# logger_connector.net
KiCad netlist of a schematic drawn in Altium Designer
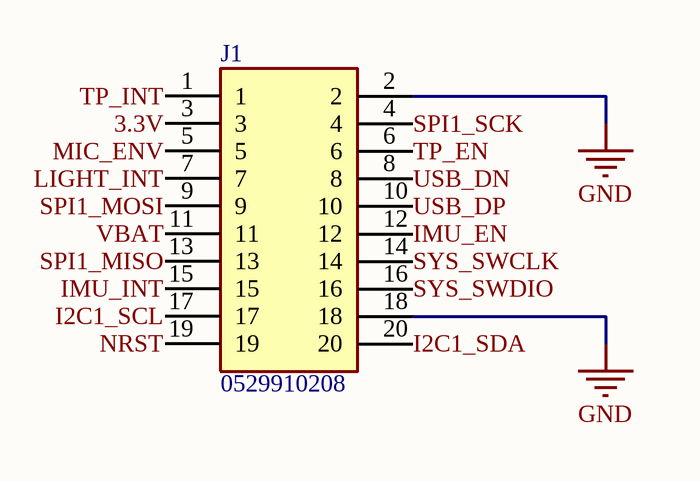
[diagram p0: logger_connector.SchDoc]

(export (version "E")
  (design (tool "Eeschema 10.0.6"))
  (components
    (comp (ref "J1")
      (value "0529910208")
      (footprint "SamacSys:0529910208")
      (description "Connector")
      (libsource (lib "*") (part "0529910208"))
    )
  )
  (nets
    (net (code "1") (name "/3.3V") (class "Default")
      (node (ref "J1") (pin "3") (pinfunction "3_3") (pintype "passive"))
    )
    (net (code "2") (name "/I2C1_SCL") (class "Default")
      (node (ref "J1") (pin "17") (pinfunction "17_17") (pintype "passive"))
    )
    (net (code "3") (name "/I2C1_SDA") (class "Default")
      (node (ref "J1") (pin "20") (pinfunction "20_20") (pintype "passive"))
    )
    (net (code "4") (name "/IMU_EN") (class "Default")
      (node (ref "J1") (pin "12") (pinfunction "12_12") (pintype "passive"))
    )
    (net (code "5") (name "/IMU_INT") (class "Default")
      (node (ref "J1") (pin "15") (pinfunction "15_15") (pintype "passive"))
    )
    (net (code "6") (name "/LIGHT_INT") (class "Default")
      (node (ref "J1") (pin "7") (pinfunction "7_7") (pintype "passive"))
    )
    (net (code "7") (name "/MIC_ENV") (class "Default")
      (node (ref "J1") (pin "5") (pinfunction "5_5") (pintype "passive"))
    )
    (net (code "8") (name "/NRST") (class "Default")
      (node (ref "J1") (pin "19") (pinfunction "19_19") (pintype "passive"))
    )
    (net (code "9") (name "/SPI1_MISO") (class "Default")
      (node (ref "J1") (pin "13") (pinfunction "13_13") (pintype "passive"))
    )
    (net (code "10") (name "/SPI1_MOSI") (class "Default")
      (node (ref "J1") (pin "9") (pinfunction "9_9") (pintype "passive"))
    )
    (net (code "11") (name "/SPI1_SCK") (class "Default")
      (node (ref "J1") (pin "4") (pinfunction "4_4") (pintype "passive"))
    )
    (net (code "12") (name "/SYS_SWCLK") (class "Default")
      (node (ref "J1") (pin "14") (pinfunction "14_14") (pintype "passive"))
    )
    (net (code "13") (name "/SYS_SWDIO") (class "Default")
      (node (ref "J1") (pin "16") (pinfunction "16_16") (pintype "passive"))
    )
    (net (code "14") (name "/TP_EN") (class "Default")
      (node (ref "J1") (pin "6") (pinfunction "6_6") (pintype "passive"))
    )
    (net (code "15") (name "/TP_INT") (class "Default")
      (node (ref "J1") (pin "1") (pinfunction "1_1") (pintype "passive"))
    )
    (net (code "16") (name "/USB_DN") (class "Default")
      (node (ref "J1") (pin "8") (pinfunction "8_8") (pintype "passive"))
    )
    (net (code "17") (name "/USB_DP") (class "Default")
      (node (ref "J1") (pin "10") (pinfunction "10_10") (pintype "passive"))
    )
    (net (code "18") (name "/VBAT") (class "Default")
      (node (ref "J1") (pin "11") (pinfunction "11_11") (pintype "passive"))
    )
    (net (code "19") (name "GND") (class "Default")
      (node (ref "J1") (pin "18") (pinfunction "18_18") (pintype "passive"))
      (node (ref "J1") (pin "2") (pinfunction "2_2") (pintype "passive"))
    )
  )
)
